# IMU_9DoF_AHRS.net
KiCad netlist of a schematic drawn in EAGLE
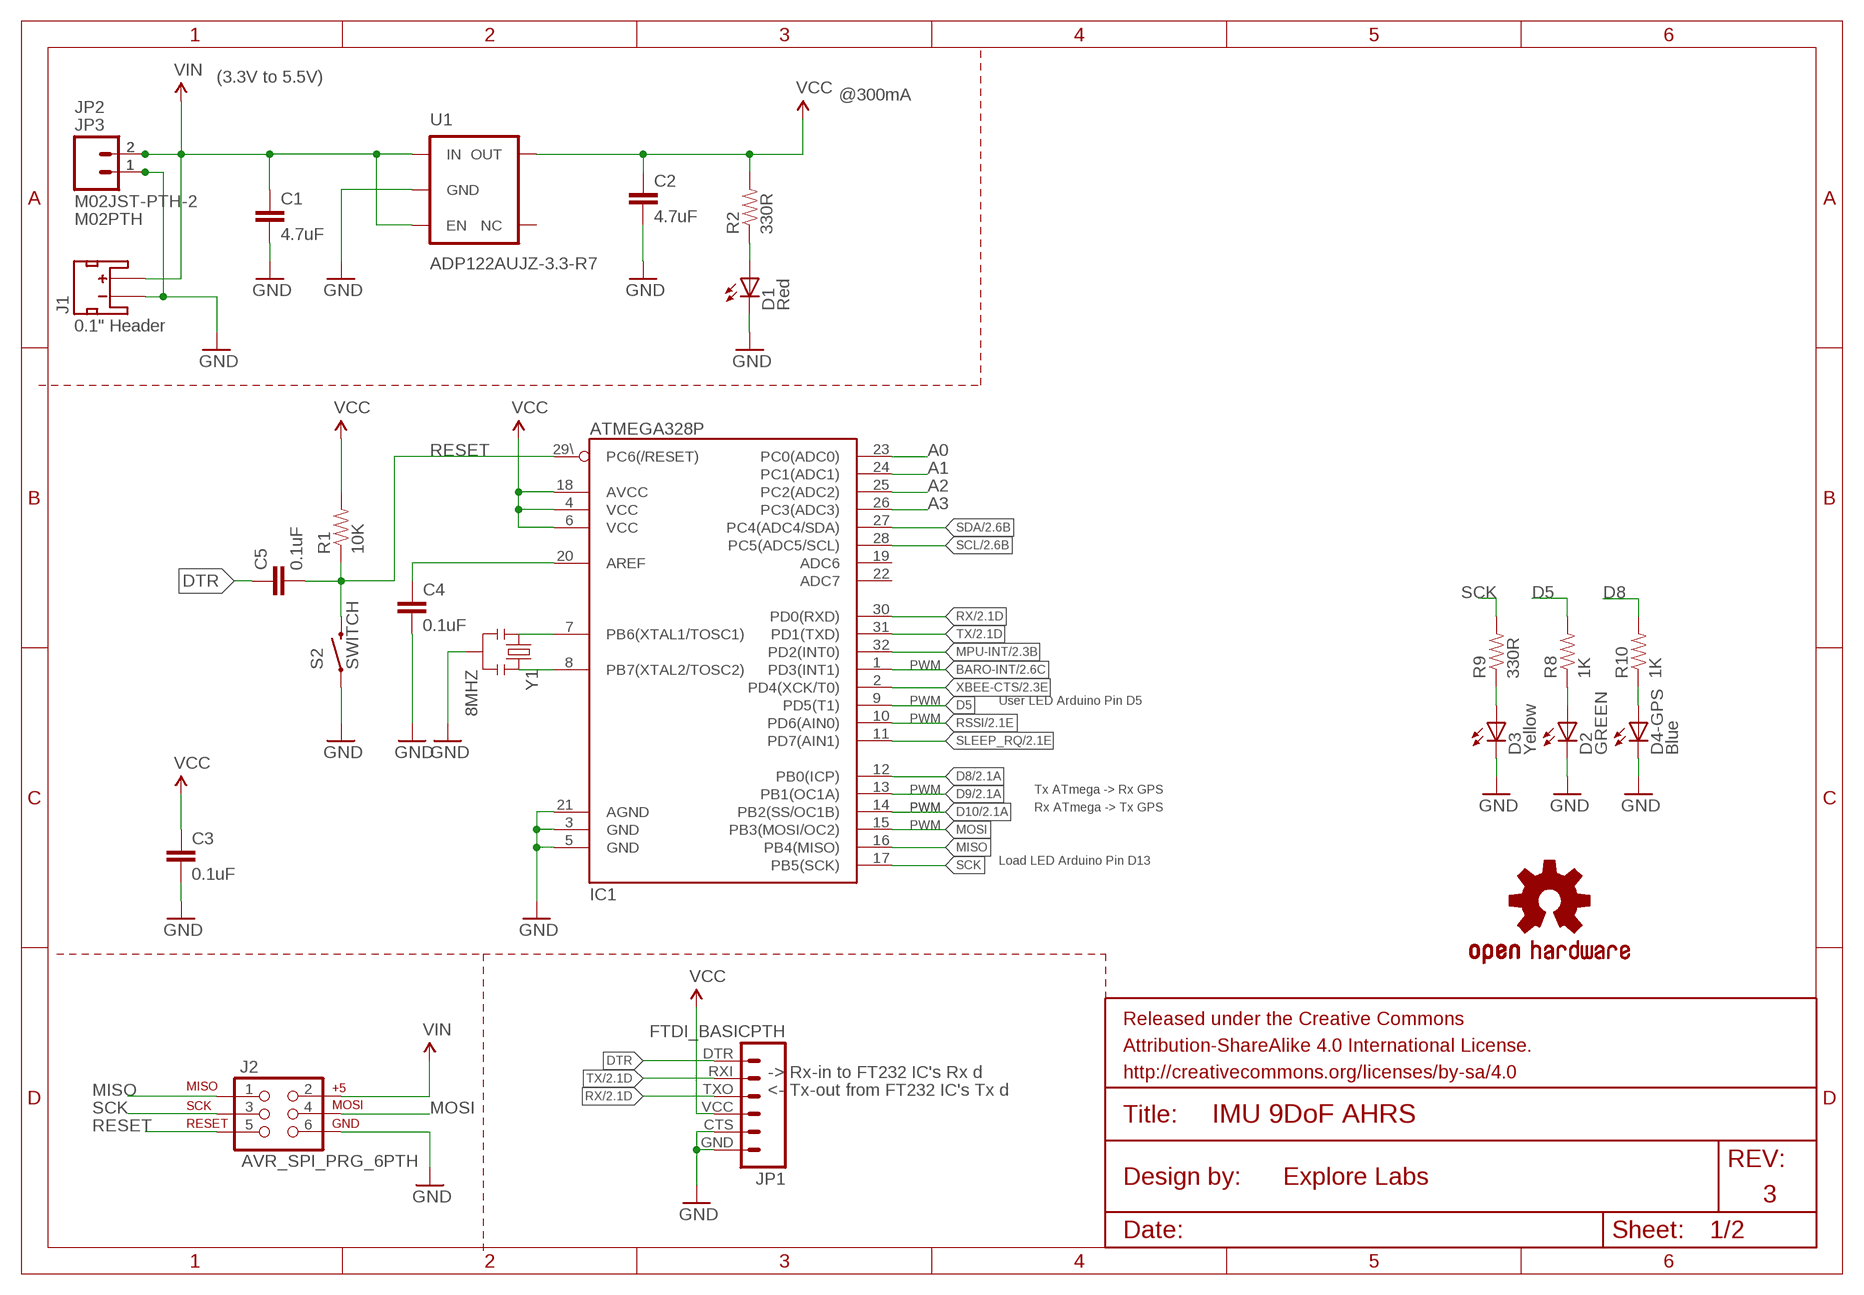
[diagram p0: schematic, sheet 1]
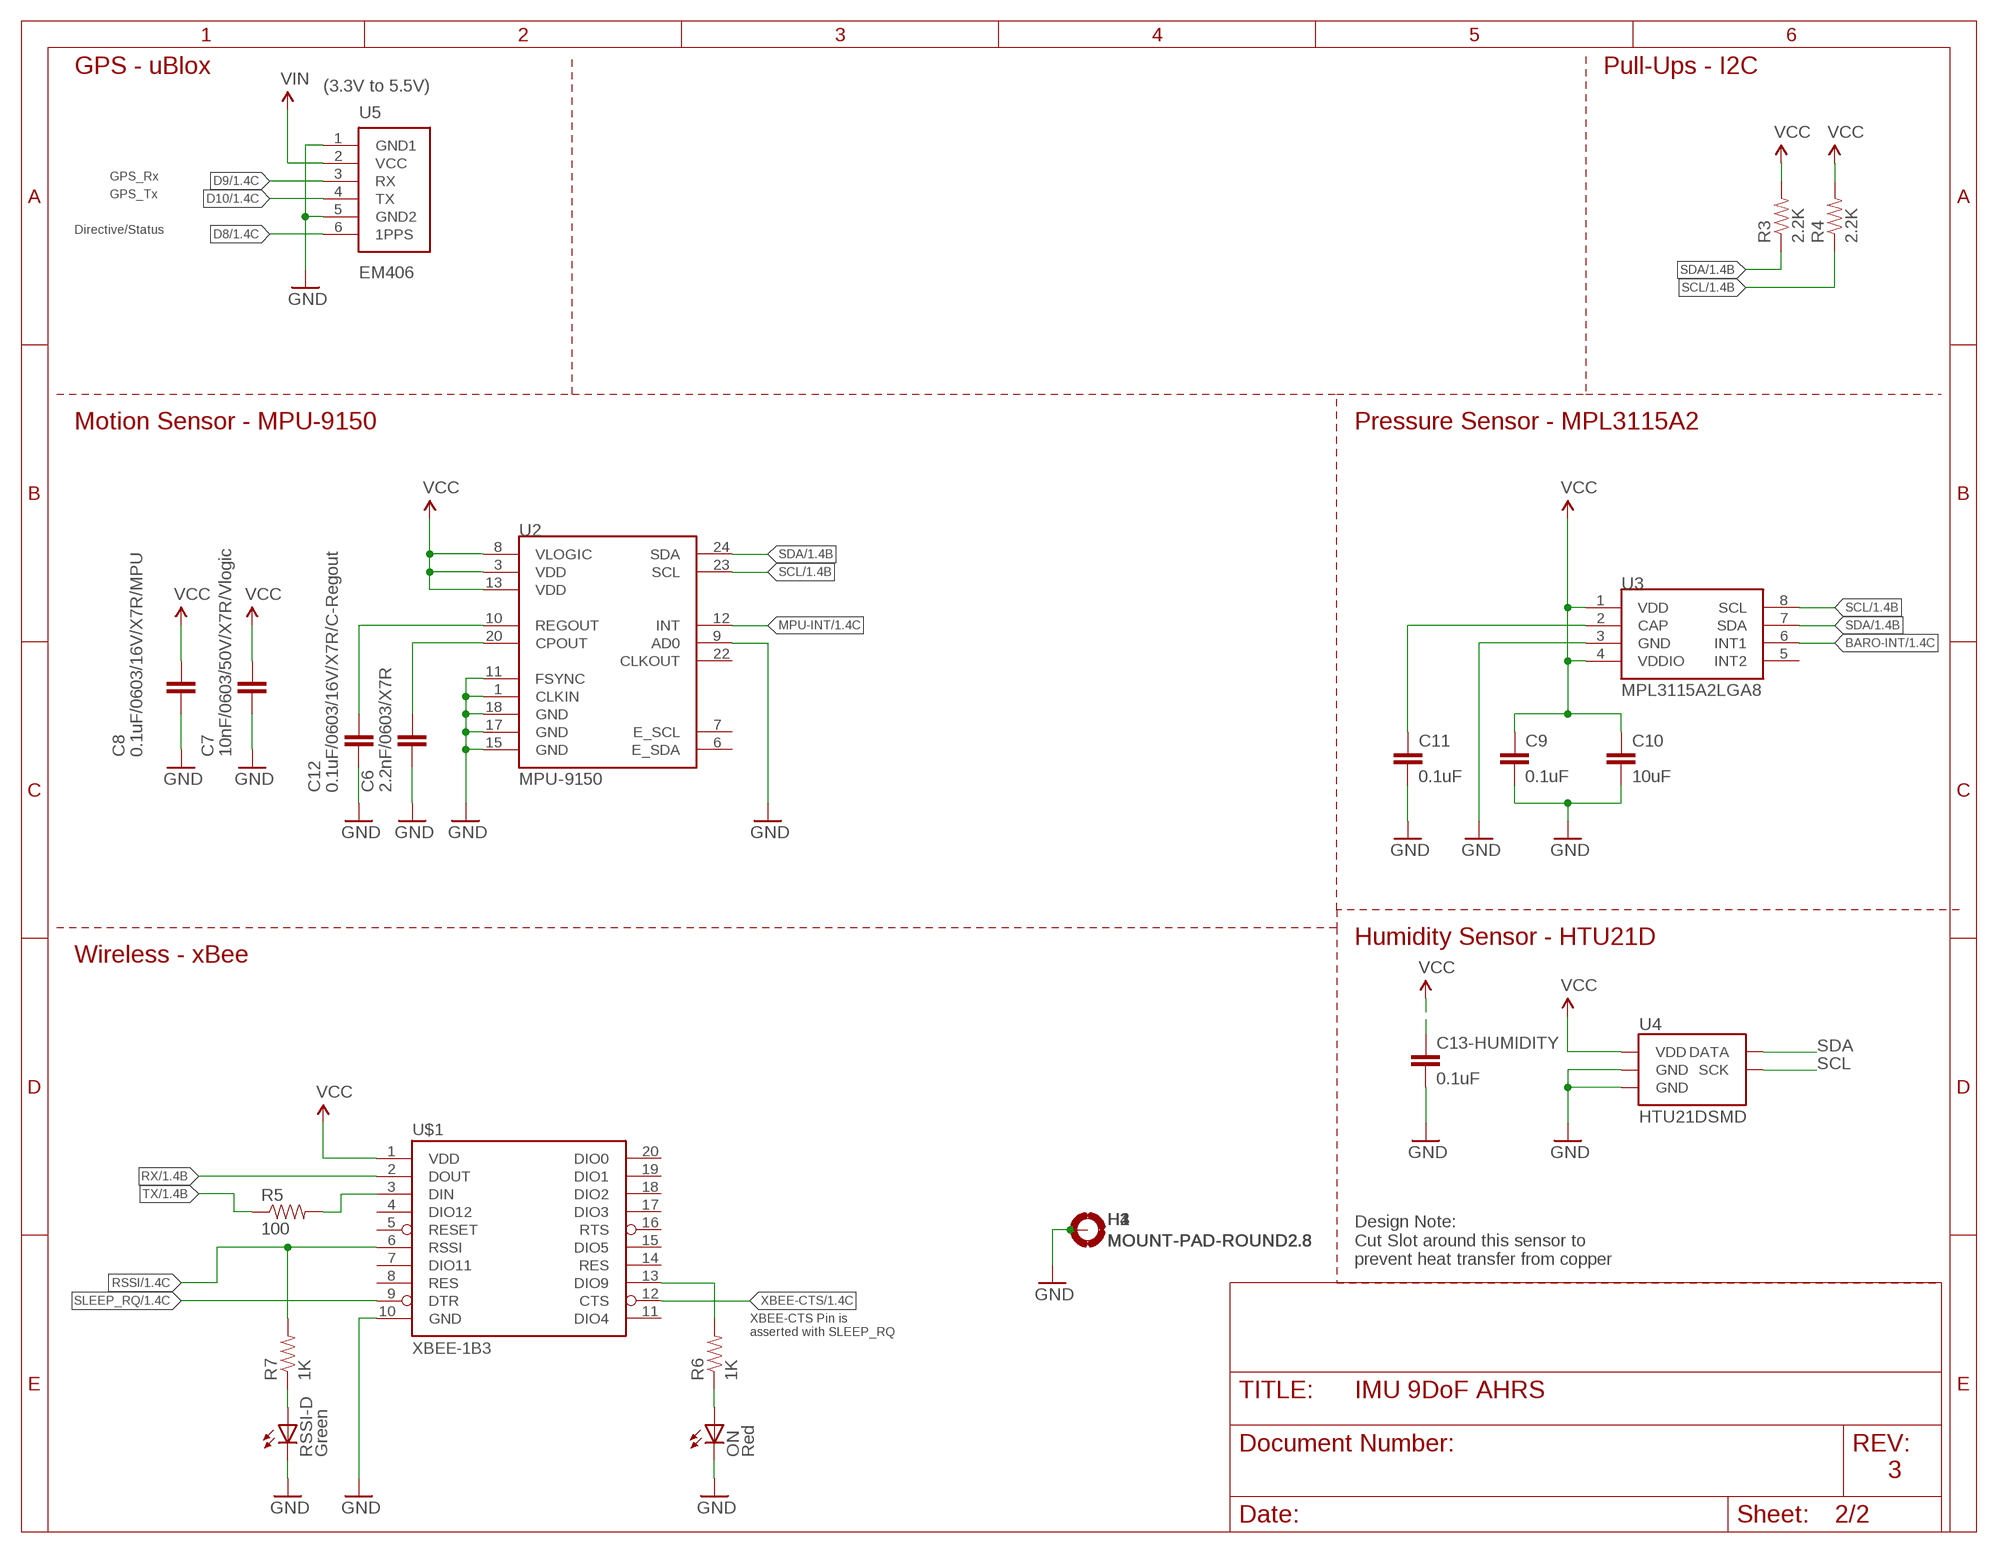
[diagram p1: schematic, sheet 2]

(export (version "E")
  (design (tool "Eeschema 10.0.6"))
  (components
    (comp (ref "C1")
      (value "4.7uF")
      (footprint "eagle-import:0603-CAP")
      (libsource (lib "eagle-import") (part "SparkFun-Passives_CAP0603-CAP"))
    )
    (comp (ref "C2")
      (value "4.7uF")
      (footprint "eagle-import:0603-CAP")
      (libsource (lib "eagle-import") (part "SparkFun-Passives_CAP0603-CAP"))
    )
    (comp (ref "C3")
      (value "0.1uF")
      (footprint "eagle-import:0603-CAP")
      (libsource (lib "eagle-import") (part "SparkFun-Passives_CAP0603-CAP"))
    )
    (comp (ref "C4")
      (value "0.1uF")
      (footprint "eagle-import:0603-CAP")
      (libsource (lib "eagle-import") (part "SparkFun-Passives_CAP0603-CAP"))
    )
    (comp (ref "C5")
      (value "0.1uF")
      (footprint "eagle-import:0603-CAP")
      (libsource (lib "eagle-import") (part "SparkFun-Passives_CAP0603-CAP"))
    )
    (comp (ref "D1")
      (value "Red")
      (footprint "eagle-import:CHIPLED_0805")
      (libsource (lib "eagle-import") (part "LEDCHIPLED_0805"))
    )
    (comp (ref "D2")
      (value "GREEN")
      (footprint "eagle-import:CHIPLED_0805")
      (libsource (lib "eagle-import") (part "LEDCHIPLED_0805"))
    )
    (comp (ref "D3")
      (value "Yellow")
      (footprint "eagle-import:CHIPLED_0805")
      (libsource (lib "eagle-import") (part "LEDCHIPLED_0805"))
    )
    (comp (ref "D4-GPS")
      (value "Blue")
      (footprint "eagle-import:CHIPLED_0805")
      (libsource (lib "eagle-import") (part "LEDCHIPLED_0805"))
    )
    (comp (ref "IC1")
      (value "ATMEGA328P")
      (footprint "eagle-import:TQFP32-08")
      (libsource (lib "eagle-import") (part "ATMEGA328_SMT"))
    )
    (comp (ref "J1")
      (value "JST_2MM_MALE")
      (footprint "eagle-import:JST-2-SMD")
      (libsource (lib "eagle-import") (part "JST_2MM_MALE"))
    )
    (comp (ref "J2")
      (value "AVR_SPI_PRG_6PTH")
      (footprint "eagle-import:2X3")
      (libsource (lib "eagle-import") (part "AVR_SPI_PRG_6PTH"))
    )
    (comp (ref "JP1")
      (value "FTDI_BASICPTH")
      (footprint "eagle-import:FTDI_BASIC")
      (libsource (lib "eagle-import") (part "FTDI_BASICPTH"))
    )
    (comp (ref "JP2")
      (value "M02JST-PTH-2")
      (footprint "eagle-import:JST-2-PTH")
      (libsource (lib "eagle-import") (part "M02JST-PTH-2"))
    )
    (comp (ref "JP3")
      (value "M02PTH")
      (footprint "eagle-import:1X02")
      (libsource (lib "eagle-import") (part "M02PTH"))
    )
    (comp (ref "LOGO4")
      (value "OSHW-LOGOBOTTOM")
      (footprint "eagle-import:OSHW-LOGO-M-BOTTOM")
      (libsource (lib "eagle-import") (part "OSHW-LOGOBOTTOM"))
    )
    (comp (ref "R1")
      (value "10K")
      (footprint "eagle-import:0603-RES")
      (libsource (lib "eagle-import") (part "RESISTOR0603-RES"))
    )
    (comp (ref "R2")
      (value "330R")
      (footprint "eagle-import:0603-RES")
      (libsource (lib "eagle-import") (part "RESISTOR0603-RES"))
    )
    (comp (ref "R8")
      (value "1K")
      (footprint "eagle-import:0603-RES")
      (libsource (lib "eagle-import") (part "RESISTOR0603-RES"))
    )
    (comp (ref "R9")
      (value "330R")
      (footprint "eagle-import:0603-RES")
      (libsource (lib "eagle-import") (part "RESISTOR0603-RES"))
    )
    (comp (ref "R10")
      (value "1K")
      (footprint "eagle-import:0603-RES")
      (libsource (lib "eagle-import") (part "RESISTOR0603-RES"))
    )
    (comp (ref "S2")
      (value "SWITCH-MOMENTARY-2-SMD-1101NE")
      (footprint "eagle-import:TACTILE-SWITCH-1101NE")
      (libsource (lib "eagle-import") (part "SWITCH-MOMENTARY-2-SMD-1101NE"))
    )
    (comp (ref "U1")
      (value "ADP122AUJZ-3.3-R7")
      (footprint "eagle-import:SOT-23-5")
      (libsource (lib "eagle-import") (part "ADP122AUJZ-3.3-R7"))
    )
    (comp (ref "Y1")
      (value "8MHZ")
      (footprint "eagle-import:RESONATOR-SMD")
      (libsource (lib "eagle-import") (part "RESONATOR8MHZ"))
    )
    (comp (ref "C6")
      (value "2.2nF/0603/X7R")
      (footprint "eagle-import:0603-CAP")
      (libsource (lib "eagle-import") (part "SparkFun-Passives_CAP0603-CAP"))
    )
    (comp (ref "C7")
      (value "10nF/0603/50V/X7R/Vlogic")
      (footprint "eagle-import:0603-CAP")
      (libsource (lib "eagle-import") (part "SparkFun-Passives_CAP0603-CAP"))
    )
    (comp (ref "C8")
      (value "0.1uF/0603/16V/X7R/MPU")
      (footprint "eagle-import:0603-CAP")
      (libsource (lib "eagle-import") (part "SparkFun-Passives_CAP0603-CAP"))
    )
    (comp (ref "C9")
      (value "0.1uF")
      (footprint "eagle-import:0603-CAP")
      (libsource (lib "eagle-import") (part "CAP0603-CAP"))
    )
    (comp (ref "C10")
      (value "10uF")
      (footprint "eagle-import:0805")
      (libsource (lib "eagle-import") (part "CAP0805"))
    )
    (comp (ref "C11")
      (value "0.1uF")
      (footprint "eagle-import:0603-CAP")
      (libsource (lib "eagle-import") (part "CAP0603-CAP"))
    )
    (comp (ref "C12")
      (value "0.1uF/0603/16V/X7R/C-Regout")
      (footprint "eagle-import:0603-CAP")
      (libsource (lib "eagle-import") (part "SparkFun-Passives_CAP0603-CAP"))
    )
    (comp (ref "C13-HUMIDITY")
      (value "0.1uF")
      (footprint "eagle-import:0603-CAP")
      (libsource (lib "eagle-import") (part "CAP0603-CAP"))
    )
    (comp (ref "H1")
      (value "MOUNT-PAD-ROUND2.8")
      (footprint "eagle-import:2,8-PAD")
      (libsource (lib "eagle-import") (part "MOUNT-PAD-ROUND2.8"))
    )
    (comp (ref "H2")
      (value "MOUNT-PAD-ROUND2.8")
      (footprint "eagle-import:2,8-PAD")
      (libsource (lib "eagle-import") (part "MOUNT-PAD-ROUND2.8"))
    )
    (comp (ref "H3")
      (value "MOUNT-PAD-ROUND2.8")
      (footprint "eagle-import:2,8-PAD")
      (libsource (lib "eagle-import") (part "MOUNT-PAD-ROUND2.8"))
    )
    (comp (ref "H4")
      (value "MOUNT-PAD-ROUND2.8")
      (footprint "eagle-import:2,8-PAD")
      (libsource (lib "eagle-import") (part "MOUNT-PAD-ROUND2.8"))
    )
    (comp (ref "ON")
      (value "Red")
      (footprint "eagle-import:CHIPLED_0805")
      (libsource (lib "eagle-import") (part "LEDCHIPLED_0805"))
    )
    (comp (ref "R3")
      (value "2.2K")
      (footprint "eagle-import:0603-RES")
      (libsource (lib "eagle-import") (part "RESISTOR0603-RES"))
    )
    (comp (ref "R4")
      (value "2.2K")
      (footprint "eagle-import:0603-RES")
      (libsource (lib "eagle-import") (part "RESISTOR0603-RES"))
    )
    (comp (ref "R5")
      (value "100")
      (footprint "eagle-import:0603-RES")
      (libsource (lib "eagle-import") (part "RESISTOR0603-RES"))
    )
    (comp (ref "R6")
      (value "1K")
      (footprint "eagle-import:0603-RES")
      (libsource (lib "eagle-import") (part "RESISTOR0603-RES"))
    )
    (comp (ref "R7")
      (value "1K")
      (footprint "eagle-import:0603-RES")
      (libsource (lib "eagle-import") (part "RESISTOR0603-RES"))
    )
    (comp (ref "RSSI-D")
      (value "Green")
      (footprint "eagle-import:CHIPLED_0805")
      (libsource (lib "eagle-import") (part "LEDCHIPLED_0805"))
    )
    (comp (ref "U$1")
      (value "XBEE-1B3")
      (footprint "eagle-import:XBEE-SMD")
      (libsource (lib "eagle-import") (part "XBEE-1B3"))
    )
    (comp (ref "U2")
      (value "MPU-9150QFN-24-NP")
      (footprint "eagle-import:QFN-24-NP")
      (libsource (lib "eagle-import") (part "MPU-9150QFN-24-NP"))
    )
    (comp (ref "U3")
      (value "MPL3115A2LGA8")
      (footprint "eagle-import:LGA8")
      (libsource (lib "eagle-import") (part "MPL3115A2LGA8"))
    )
    (comp (ref "U4")
      (value "HTU21DSMD")
      (footprint "eagle-import:HTU21D")
      (libsource (lib "eagle-import") (part "HTU21DSMD"))
    )
    (comp (ref "U5")
      (value "EM406")
      (footprint "eagle-import:EM406")
      (libsource (lib "eagle-import") (part "EM406"))
    )
  )
  (nets
    (net (code "1") (name "A0") (class "Default")
      (node (ref "IC1") (pin "23") (pinfunction "PC0(ADC0)_23") (pintype "bidirectional"))
    )
    (net (code "2") (name "A1") (class "Default")
      (node (ref "IC1") (pin "24") (pinfunction "PC1(ADC1)_24") (pintype "bidirectional"))
    )
    (net (code "3") (name "A2") (class "Default")
      (node (ref "IC1") (pin "25") (pinfunction "PC2(ADC2)_25") (pintype "bidirectional"))
    )
    (net (code "4") (name "A3") (class "Default")
      (node (ref "IC1") (pin "26") (pinfunction "PC3(ADC3)_26") (pintype "bidirectional"))
    )
    (net (code "5") (name "BARO-INT") (class "Default")
      (node (ref "IC1") (pin "1") (pinfunction "PD3(INT1)_1") (pintype "bidirectional"))
      (node (ref "U3") (pin "6") (pinfunction "INT1_6") (pintype "bidirectional"))
    )
    (net (code "6") (name "D5") (class "Default")
      (node (ref "IC1") (pin "9") (pinfunction "PD5(T1)_9") (pintype "bidirectional"))
      (node (ref "R8") (pin "2") (pinfunction "2_2") (pintype "passive"))
    )
    (net (code "7") (name "D8") (class "Default")
      (node (ref "IC1") (pin "12") (pinfunction "PB0(ICP)_12") (pintype "bidirectional"))
      (node (ref "R10") (pin "2") (pinfunction "2_2") (pintype "passive"))
      (node (ref "U5") (pin "6") (pinfunction "1PPS_6") (pintype "bidirectional"))
    )
    (net (code "8") (name "D9") (class "Default")
      (node (ref "IC1") (pin "13") (pinfunction "PB1(OC1A)_13") (pintype "bidirectional"))
      (node (ref "U5") (pin "3") (pinfunction "RX_3") (pintype "bidirectional"))
    )
    (net (code "9") (name "D10") (class "Default")
      (node (ref "IC1") (pin "14") (pinfunction "PB2(SS/OC1B)_14") (pintype "bidirectional"))
      (node (ref "U5") (pin "4") (pinfunction "TX_4") (pintype "bidirectional"))
    )
    (net (code "10") (name "DTR") (class "Default")
      (node (ref "C5") (pin "1") (pinfunction "1_1") (pintype "passive"))
      (node (ref "JP1") (pin "DTR") (pinfunction "1_DTR") (pintype "passive"))
    )
    (net (code "11") (name "GND") (class "Default")
      (node (ref "C1") (pin "2") (pinfunction "2_2") (pintype "passive"))
      (node (ref "C10") (pin "2") (pinfunction "2_2") (pintype "passive"))
      (node (ref "C11") (pin "2") (pinfunction "2_2") (pintype "passive"))
      (node (ref "C12") (pin "2") (pinfunction "2_2") (pintype "passive"))
      (node (ref "C13-HUMIDITY") (pin "2") (pinfunction "2_2") (pintype "passive"))
      (node (ref "C2") (pin "2") (pinfunction "2_2") (pintype "passive"))
      (node (ref "C3") (pin "2") (pinfunction "2_2") (pintype "passive"))
      (node (ref "C4") (pin "2") (pinfunction "2_2") (pintype "passive"))
      (node (ref "C6") (pin "2") (pinfunction "2_2") (pintype "passive"))
      (node (ref "C7") (pin "2") (pinfunction "2_2") (pintype "passive"))
      (node (ref "C8") (pin "2") (pinfunction "2_2") (pintype "passive"))
      (node (ref "C9") (pin "2") (pinfunction "2_2") (pintype "passive"))
      (node (ref "D1") (pin "C") (pinfunction "C_C") (pintype "passive"))
      (node (ref "D2") (pin "C") (pinfunction "C_C") (pintype "passive"))
      (node (ref "D3") (pin "C") (pinfunction "C_C") (pintype "passive"))
      (node (ref "D4-GPS") (pin "C") (pinfunction "C_C") (pintype "passive"))
      (node (ref "H1") (pin "B2,8") (pinfunction "MOUNT_B2,8") (pintype "passive"))
      (node (ref "H2") (pin "B2,8") (pinfunction "MOUNT_B2,8") (pintype "passive"))
      (node (ref "H3") (pin "B2,8") (pinfunction "MOUNT_B2,8") (pintype "passive"))
      (node (ref "H4") (pin "B2,8") (pinfunction "MOUNT_B2,8") (pintype "passive"))
      (node (ref "IC1") (pin "21") (pinfunction "AGND_21") (pintype "bidirectional"))
      (node (ref "IC1") (pin "3") (pinfunction "GND_3") (pintype "bidirectional"))
      (node (ref "IC1") (pin "5") (pinfunction "GND_5") (pintype "bidirectional"))
      (node (ref "J1") (pin "1") (pinfunction "-_1") (pintype "bidirectional"))
      (node (ref "J2") (pin "6") (pinfunction "6_6") (pintype "passive"))
      (node (ref "JP1") (pin "CTS") (pinfunction "5_CTS") (pintype "passive"))
      (node (ref "JP1") (pin "GND") (pinfunction "6_GND") (pintype "passive"))
      (node (ref "JP2") (pin "1") (pinfunction "1_1") (pintype "passive"))
      (node (ref "JP3") (pin "1") (pinfunction "1_1") (pintype "passive"))
      (node (ref "ON") (pin "C") (pinfunction "C_C") (pintype "passive"))
      (node (ref "RSSI-D") (pin "C") (pinfunction "C_C") (pintype "passive"))
      (node (ref "S2") (pin "P$1") (pinfunction "1_P$1") (pintype "passive"))
      (node (ref "U$1") (pin "10") (pinfunction "GND_10") (pintype "power_in"))
      (node (ref "U1") (pin "2") (pinfunction "GND_2") (pintype "input"))
      (node (ref "U2") (pin "1") (pinfunction "CLKIN_1") (pintype "bidirectional"))
      (node (ref "U2") (pin "11") (pinfunction "FSYNC_11") (pintype "bidirectional"))
      (node (ref "U2") (pin "15") (pinfunction "GND_15") (pintype "bidirectional"))
      (node (ref "U2") (pin "17") (pinfunction "GND_17") (pintype "bidirectional"))
      (node (ref "U2") (pin "18") (pinfunction "GND_18") (pintype "bidirectional"))
      (node (ref "U2") (pin "9") (pinfunction "AD0_9") (pintype "bidirectional"))
      (node (ref "U3") (pin "3") (pinfunction "GND_3") (pintype "bidirectional"))
      (node (ref "U4") (pin "7") (pinfunction "GND_7") (pintype "power_in"))
      (node (ref "U4") (pin "GND") (pinfunction "GND_GND") (pintype "power_in"))
      (node (ref "U5") (pin "1") (pinfunction "GND1_1") (pintype "bidirectional"))
      (node (ref "U5") (pin "5") (pinfunction "GND2_5") (pintype "bidirectional"))
      (node (ref "Y1") (pin "2") (pinfunction "2_2") (pintype "passive"))
    )
    (net (code "12") (name "MISO") (class "Default")
      (node (ref "IC1") (pin "16") (pinfunction "PB4(MISO)_16") (pintype "bidirectional"))
      (node (ref "J2") (pin "1") (pinfunction "1_1") (pintype "passive"))
    )
    (net (code "13") (name "MOSI") (class "Default")
      (node (ref "IC1") (pin "15") (pinfunction "PB3(MOSI/OC2)_15") (pintype "bidirectional"))
      (node (ref "J2") (pin "4") (pinfunction "4_4") (pintype "passive"))
    )
    (net (code "14") (name "MPU-INT") (class "Default")
      (node (ref "IC1") (pin "32") (pinfunction "PD2(INT0)_32") (pintype "bidirectional"))
      (node (ref "U2") (pin "12") (pinfunction "INT_12") (pintype "bidirectional"))
    )
    (net (code "15") (name "Net-(D1-PadA)") (class "Default")
      (node (ref "D1") (pin "A") (pinfunction "A_A") (pintype "passive"))
      (node (ref "R2") (pin "1") (pinfunction "1_1") (pintype "passive"))
    )
    (net (code "16") (name "Net-(D2-PadA)") (class "Default")
      (node (ref "D2") (pin "A") (pinfunction "A_A") (pintype "passive"))
      (node (ref "R8") (pin "1") (pinfunction "1_1") (pintype "passive"))
    )
    (net (code "17") (name "Net-(D3-PadA)") (class "Default")
      (node (ref "D3") (pin "A") (pinfunction "A_A") (pintype "passive"))
      (node (ref "R9") (pin "1") (pinfunction "1_1") (pintype "passive"))
    )
    (net (code "18") (name "Net-(D4-GPS-PadA)") (class "Default")
      (node (ref "D4-GPS") (pin "A") (pinfunction "A_A") (pintype "passive"))
      (node (ref "R10") (pin "1") (pinfunction "1_1") (pintype "passive"))
    )
    (net (code "19") (name "Net-(IC1-AREF)") (class "Default")
      (node (ref "C4") (pin "1") (pinfunction "1_1") (pintype "passive"))
      (node (ref "IC1") (pin "20") (pinfunction "AREF_20") (pintype "bidirectional"))
    )
    (net (code "20") (name "Net-(IC1-PB6(XTAL1{slash}TOSC1))") (class "Default")
      (node (ref "IC1") (pin "7") (pinfunction "PB6(XTAL1/TOSC1)_7") (pintype "bidirectional"))
      (node (ref "Y1") (pin "1") (pinfunction "1_1") (pintype "passive"))
    )
    (net (code "21") (name "Net-(IC1-PB7(XTAL2{slash}TOSC2))") (class "Default")
      (node (ref "IC1") (pin "8") (pinfunction "PB7(XTAL2/TOSC2)_8") (pintype "bidirectional"))
      (node (ref "Y1") (pin "3") (pinfunction "3_3") (pintype "passive"))
    )
    (net (code "22") (name "Net-(ON-PadA)") (class "Default")
      (node (ref "ON") (pin "A") (pinfunction "A_A") (pintype "passive"))
      (node (ref "R6") (pin "1") (pinfunction "1_1") (pintype "passive"))
    )
    (net (code "23") (name "Net-(R7-Pad1)") (class "Default")
      (node (ref "R7") (pin "1") (pinfunction "1_1") (pintype "passive"))
      (node (ref "RSSI-D") (pin "A") (pinfunction "A_A") (pintype "passive"))
    )
    (net (code "24") (name "Net-(U$1-DIN)") (class "Default")
      (node (ref "R5") (pin "2") (pinfunction "2_2") (pintype "passive"))
      (node (ref "U$1") (pin "3") (pinfunction "DIN_3") (pintype "input"))
    )
    (net (code "25") (name "Net-(U$1-DIO9)") (class "Default")
      (node (ref "R6") (pin "2") (pinfunction "2_2") (pintype "passive"))
      (node (ref "U$1") (pin "13") (pinfunction "DIO9_13") (pintype "bidirectional"))
    )
    (net (code "26") (name "Net-(U2-CPOUT)") (class "Default")
      (node (ref "C6") (pin "1") (pinfunction "1_1") (pintype "passive"))
      (node (ref "U2") (pin "20") (pinfunction "CPOUT_20") (pintype "bidirectional"))
    )
    (net (code "27") (name "Net-(U2-REGOUT)") (class "Default")
      (node (ref "C12") (pin "1") (pinfunction "1_1") (pintype "passive"))
      (node (ref "U2") (pin "10") (pinfunction "REGOUT_10") (pintype "bidirectional"))
    )
    (net (code "28") (name "Net-(U3-CAP)") (class "Default")
      (node (ref "C11") (pin "1") (pinfunction "1_1") (pintype "passive"))
      (node (ref "U3") (pin "2") (pinfunction "CAP_2") (pintype "bidirectional"))
    )
    (net (code "29") (name "RESET") (class "Default")
      (node (ref "C5") (pin "2") (pinfunction "2_2") (pintype "passive"))
      (node (ref "IC1") (pin "29\\") (pinfunction "PC6(/RESET)_29\\") (pintype "bidirectional"))
      (node (ref "J2") (pin "5") (pinfunction "5_5") (pintype "passive"))
      (node (ref "R1") (pin "1") (pinfunction "1_1") (pintype "passive"))
      (node (ref "S2") (pin "P$2") (pinfunction "2_P$2") (pintype "passive"))
    )
    (net (code "30") (name "RSSI") (class "Default")
      (node (ref "IC1") (pin "10") (pinfunction "PD6(AIN0)_10") (pintype "bidirectional"))
      (node (ref "R7") (pin "2") (pinfunction "2_2") (pintype "passive"))
      (node (ref "U$1") (pin "6") (pinfunction "RSSI_6") (pintype "bidirectional"))
    )
    (net (code "31") (name "RX") (class "Default")
      (node (ref "IC1") (pin "30") (pinfunction "PD0(RXD)_30") (pintype "bidirectional"))
      (node (ref "JP1") (pin "TXO") (pinfunction "3_TXO") (pintype "passive"))
      (node (ref "U$1") (pin "2") (pinfunction "DOUT_2") (pintype "output"))
    )
    (net (code "32") (name "SCK") (class "Default")
      (node (ref "IC1") (pin "17") (pinfunction "PB5(SCK)_17") (pintype "bidirectional"))
      (node (ref "J2") (pin "3") (pinfunction "3_3") (pintype "passive"))
      (node (ref "R9") (pin "2") (pinfunction "2_2") (pintype "passive"))
    )
    (net (code "33") (name "SCL") (class "Default")
      (node (ref "IC1") (pin "28") (pinfunction "PC5(ADC5/SCL)_28") (pintype "bidirectional"))
      (node (ref "R4") (pin "1") (pinfunction "1_1") (pintype "passive"))
      (node (ref "U2") (pin "23") (pinfunction "SCL_23") (pintype "bidirectional"))
      (node (ref "U3") (pin "8") (pinfunction "SCL_8") (pintype "bidirectional"))
      (node (ref "U4") (pin "SCK") (pinfunction "SCK_SCK") (pintype "input"))
    )
    (net (code "34") (name "SDA") (class "Default")
      (node (ref "IC1") (pin "27") (pinfunction "PC4(ADC4/SDA)_27") (pintype "bidirectional"))
      (node (ref "R3") (pin "1") (pinfunction "1_1") (pintype "passive"))
      (node (ref "U2") (pin "24") (pinfunction "SDA_24") (pintype "bidirectional"))
      (node (ref "U3") (pin "7") (pinfunction "SDA_7") (pintype "bidirectional"))
      (node (ref "U4") (pin "DATA") (pinfunction "DATA_DATA") (pintype "bidirectional"))
    )
    (net (code "35") (name "SLEEP_RQ") (class "Default")
      (node (ref "IC1") (pin "11") (pinfunction "PD7(AIN1)_11") (pintype "bidirectional"))
      (node (ref "U$1") (pin "9") (pinfunction "DTR_9") (pintype "bidirectional"))
    )
    (net (code "36") (name "TX") (class "Default")
      (node (ref "IC1") (pin "31") (pinfunction "PD1(TXD)_31") (pintype "bidirectional"))
      (node (ref "JP1") (pin "RXI") (pinfunction "2_RXI") (pintype "passive"))
      (node (ref "R5") (pin "1") (pinfunction "1_1") (pintype "passive"))
    )
    (net (code "37") (name "VCC") (class "Default")
      (node (ref "C10") (pin "1") (pinfunction "1_1") (pintype "passive"))
      (node (ref "C13-HUMIDITY") (pin "1") (pinfunction "1_1") (pintype "passive"))
      (node (ref "C2") (pin "1") (pinfunction "1_1") (pintype "passive"))
      (node (ref "C3") (pin "1") (pinfunction "1_1") (pintype "passive"))
      (node (ref "C7") (pin "1") (pinfunction "1_1") (pintype "passive"))
      (node (ref "C8") (pin "1") (pinfunction "1_1") (pintype "passive"))
      (node (ref "C9") (pin "1") (pinfunction "1_1") (pintype "passive"))
      (node (ref "IC1") (pin "18") (pinfunction "AVCC_18") (pintype "bidirectional"))
      (node (ref "IC1") (pin "4") (pinfunction "VCC_4") (pintype "bidirectional"))
      (node (ref "IC1") (pin "6") (pinfunction "VCC_6") (pintype "bidirectional"))
      (node (ref "JP1") (pin "VCC") (pinfunction "4_VCC") (pintype "passive"))
      (node (ref "R1") (pin "2") (pinfunction "2_2") (pintype "passive"))
      (node (ref "R2") (pin "2") (pinfunction "2_2") (pintype "passive"))
      (node (ref "R3") (pin "2") (pinfunction "2_2") (pintype "passive"))
      (node (ref "R4") (pin "2") (pinfunction "2_2") (pintype "passive"))
      (node (ref "U$1") (pin "1") (pinfunction "VDD_1") (pintype "power_in"))
      (node (ref "U1") (pin "5") (pinfunction "OUT_5") (pintype "passive"))
      (node (ref "U2") (pin "13") (pinfunction "VDD_13") (pintype "bidirectional"))
      (node (ref "U2") (pin "3") (pinfunction "VDD_3") (pintype "bidirectional"))
      (node (ref "U2") (pin "8") (pinfunction "VLOGIC_8") (pintype "bidirectional"))
      (node (ref "U3") (pin "1") (pinfunction "VDD_1") (pintype "bidirectional"))
      (node (ref "U3") (pin "4") (pinfunction "VDDIO_4") (pintype "bidirectional"))
      (node (ref "U4") (pin "VDD") (pinfunction "VDD_VDD") (pintype "power_in"))
    )
    (net (code "38") (name "VIN") (class "Default")
      (node (ref "C1") (pin "1") (pinfunction "1_1") (pintype "passive"))
      (node (ref "J1") (pin "2") (pinfunction "+_2") (pintype "bidirectional"))
      (node (ref "J2") (pin "2") (pinfunction "2_2") (pintype "passive"))
      (node (ref "JP2") (pin "2") (pinfunction "2_2") (pintype "passive"))
      (node (ref "JP3") (pin "2") (pinfunction "2_2") (pintype "passive"))
      (node (ref "U1") (pin "1") (pinfunction "IN_1") (pintype "input"))
      (node (ref "U1") (pin "3") (pinfunction "EN_3") (pintype "input"))
      (node (ref "U5") (pin "2") (pinfunction "VCC_2") (pintype "bidirectional"))
    )
    (net (code "39") (name "XBEE-CTS") (class "Default")
      (node (ref "IC1") (pin "2") (pinfunction "PD4(XCK/T0)_2") (pintype "bidirectional"))
      (node (ref "U$1") (pin "12") (pinfunction "CTS_12") (pintype "output"))
    )
    (net (code "40") (name "unconnected-(IC1-ADC6-Pad19)") (class "Default")
      (node (ref "IC1") (pin "19") (pinfunction "ADC6_19") (pintype "bidirectional"))
    )
    (net (code "41") (name "unconnected-(IC1-ADC7-Pad22)") (class "Default")
      (node (ref "IC1") (pin "22") (pinfunction "ADC7_22") (pintype "bidirectional"))
    )
    (net (code "42") (name "unconnected-(J1-PAD1-PadNC1)") (class "Default")
      (node (ref "J1") (pin "NC1") (pinfunction "PAD1_NC1") (pintype "bidirectional"))
    )
    (net (code "43") (name "unconnected-(J1-PAD2-PadNC2)") (class "Default")
      (node (ref "J1") (pin "NC2") (pinfunction "PAD2_NC2") (pintype "bidirectional"))
    )
    (net (code "44") (name "unconnected-(U$1-DIO0-Pad20)") (class "Default")
      (node (ref "U$1") (pin "20") (pinfunction "DIO0_20") (pintype "bidirectional"))
    )
    (net (code "45") (name "unconnected-(U$1-DIO1-Pad19)") (class "Default")
      (node (ref "U$1") (pin "19") (pinfunction "DIO1_19") (pintype "bidirectional"))
    )
    (net (code "46") (name "unconnected-(U$1-DIO2-Pad18)") (class "Default")
      (node (ref "U$1") (pin "18") (pinfunction "DIO2_18") (pintype "bidirectional"))
    )
    (net (code "47") (name "unconnected-(U$1-DIO3-Pad17)") (class "Default")
      (node (ref "U$1") (pin "17") (pinfunction "DIO3_17") (pintype "bidirectional"))
    )
    (net (code "48") (name "unconnected-(U$1-DIO4-Pad11)") (class "Default")
      (node (ref "U$1") (pin "11") (pinfunction "DIO4_11") (pintype "bidirectional"))
    )
    (net (code "49") (name "unconnected-(U$1-DIO5-Pad15)") (class "Default")
      (node (ref "U$1") (pin "15") (pinfunction "DIO5_15") (pintype "bidirectional"))
    )
    (net (code "50") (name "unconnected-(U$1-DIO11-Pad7)") (class "Default")
      (node (ref "U$1") (pin "7") (pinfunction "DIO11_7") (pintype "bidirectional"))
    )
    (net (code "51") (name "unconnected-(U$1-DIO12-Pad4)") (class "Default")
      (node (ref "U$1") (pin "4") (pinfunction "DIO12_4") (pintype "bidirectional"))
    )
    (net (code "52") (name "unconnected-(U$1-RES-Pad8)") (class "Default")
      (node (ref "U$1") (pin "8") (pinfunction "RES_8") (pintype "bidirectional"))
    )
    (net (code "53") (name "unconnected-(U$1-RES-Pad14)") (class "Default")
      (node (ref "U$1") (pin "14") (pinfunction "RES_14") (pintype "bidirectional"))
    )
    (net (code "54") (name "unconnected-(U$1-RESET-Pad5)") (class "Default")
      (node (ref "U$1") (pin "5") (pinfunction "RESET_5") (pintype "input"))
    )
    (net (code "55") (name "unconnected-(U$1-RTS-Pad16)") (class "Default")
      (node (ref "U$1") (pin "16") (pinfunction "RTS_16") (pintype "input"))
    )
    (net (code "56") (name "unconnected-(U1-NC-Pad4)") (class "Default")
      (node (ref "U1") (pin "4") (pinfunction "NC_4") (pintype "input"))
    )
    (net (code "57") (name "unconnected-(U2-CLKOUT-Pad22)") (class "Default")
      (node (ref "U2") (pin "22") (pinfunction "CLKOUT_22") (pintype "bidirectional"))
    )
    (net (code "58") (name "unconnected-(U2-E_SCL-Pad7)") (class "Default")
      (node (ref "U2") (pin "7") (pinfunction "E_SCL_7") (pintype "bidirectional"))
    )
    (net (code "59") (name "unconnected-(U2-E_SDA-Pad6)") (class "Default")
      (node (ref "U2") (pin "6") (pinfunction "E_SDA_6") (pintype "bidirectional"))
    )
    (net (code "60") (name "unconnected-(U3-INT2-Pad5)") (class "Default")
      (node (ref "U3") (pin "5") (pinfunction "INT2_5") (pintype "bidirectional"))
    )
  )
)
